# Sheet2.net
KiCad netlist of a schematic drawn in Altium Designer
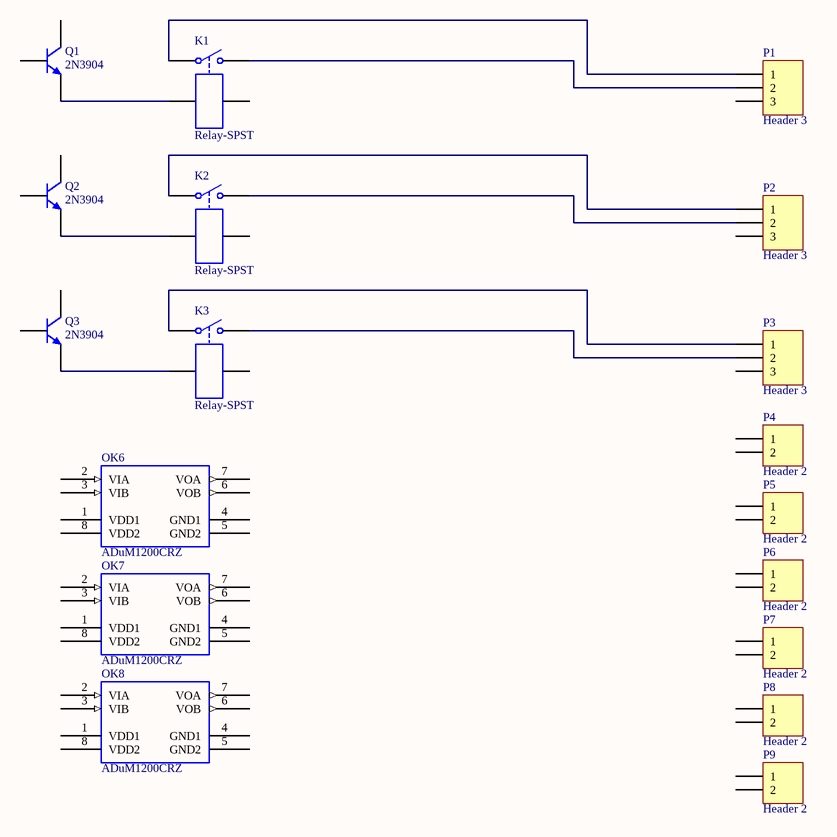
[diagram p0: Sheet2.SchDoc]

(export (version "E")
  (design (tool "Eeschema 10.0.6"))
  (components
    (comp (ref "K1")
      (value "Relay-SPST")
      (footprint "DIP-P4")
      (description "Single-Pole Single-Throw Relay")
      (fields (field (name "PUBLISHER") "Altium Limited"))
      (libsource (lib "Miscellaneous Devices") (part "Relay-SPST"))
    )
    (comp (ref "K2")
      (value "Relay-SPST")
      (footprint "DIP-P4")
      (description "Single-Pole Single-Throw Relay")
      (fields (field (name "PUBLISHER") "Altium Limited"))
      (libsource (lib "Miscellaneous Devices") (part "Relay-SPST"))
    )
    (comp (ref "K3")
      (value "Relay-SPST")
      (footprint "DIP-P4")
      (description "Single-Pole Single-Throw Relay")
      (fields (field (name "PUBLISHER") "Altium Limited"))
      (libsource (lib "Miscellaneous Devices") (part "Relay-SPST"))
    )
    (comp (ref "OK6") (value "ADuM1200CRZ") (libsource (lib "PCB_OBOB") (part "ADuM1200CRZ")))
    (comp (ref "OK7") (value "ADuM1200CRZ") (libsource (lib "PCB_OBOB") (part "ADuM1200CRZ")))
    (comp (ref "OK8") (value "ADuM1200CRZ") (libsource (lib "PCB_OBOB") (part "ADuM1200CRZ")))
    (comp (ref "P1")
      (value "Header 3")
      (footprint "HDR1X3")
      (description "Header, 3-Pin")
      (fields (field (name "PUBLISHER") "Altium Limited"))
      (libsource (lib "Miscellaneous Connectors") (part "Header 3"))
    )
    (comp (ref "P2")
      (value "Header 3")
      (footprint "HDR1X3")
      (description "Header, 3-Pin")
      (fields (field (name "PUBLISHER") "Altium Limited"))
      (libsource (lib "Miscellaneous Connectors") (part "Header 3"))
    )
    (comp (ref "P3")
      (value "Header 3")
      (footprint "HDR1X3")
      (description "Header, 3-Pin")
      (fields (field (name "PUBLISHER") "Altium Limited"))
      (libsource (lib "Miscellaneous Connectors") (part "Header 3"))
    )
    (comp (ref "P4")
      (value "Header 2")
      (footprint "HDR1X2")
      (description "Header, 2-Pin")
      (fields (field (name "PUBLISHER") "Altium Limited"))
      (libsource (lib "Miscellaneous Connectors") (part "Header 2"))
    )
    (comp (ref "P5")
      (value "Header 2")
      (footprint "HDR1X2")
      (description "Header, 2-Pin")
      (fields (field (name "PUBLISHER") "Altium Limited"))
      (libsource (lib "Miscellaneous Connectors") (part "Header 2"))
    )
    (comp (ref "P6")
      (value "Header 2")
      (footprint "HDR1X2")
      (description "Header, 2-Pin")
      (fields (field (name "PUBLISHER") "Altium Limited"))
      (libsource (lib "Miscellaneous Connectors") (part "Header 2"))
    )
    (comp (ref "P7")
      (value "Header 2")
      (footprint "HDR1X2")
      (description "Header, 2-Pin")
      (fields (field (name "PUBLISHER") "Altium Limited"))
      (libsource (lib "Miscellaneous Connectors") (part "Header 2"))
    )
    (comp (ref "P8")
      (value "Header 2")
      (footprint "HDR1X2")
      (description "Header, 2-Pin")
      (fields (field (name "PUBLISHER") "Altium Limited"))
      (libsource (lib "Miscellaneous Connectors") (part "Header 2"))
    )
    (comp (ref "P9")
      (value "Header 2")
      (footprint "HDR1X2")
      (description "Header, 2-Pin")
      (fields (field (name "PUBLISHER") "Altium Limited"))
      (libsource (lib "Miscellaneous Connectors") (part "Header 2"))
    )
    (comp (ref "Q1")
      (value "2N3904")
      (footprint "BCY-W3/E4")
      (description "NPN General Purpose Amplifier")
      (fields (field (name "PUBLISHER") "Altium Limited"))
      (libsource (lib "Miscellaneous Devices") (part "2N3904"))
    )
    (comp (ref "Q2")
      (value "2N3904")
      (footprint "BCY-W3/E4")
      (description "NPN General Purpose Amplifier")
      (fields (field (name "PUBLISHER") "Altium Limited"))
      (libsource (lib "Miscellaneous Devices") (part "2N3904"))
    )
    (comp (ref "Q3")
      (value "2N3904")
      (footprint "BCY-W3/E4")
      (description "NPN General Purpose Amplifier")
      (fields (field (name "PUBLISHER") "Altium Limited"))
      (libsource (lib "Miscellaneous Devices") (part "2N3904"))
    )
  )
  (nets
    (net (code "1") (name "Net-(K1-Pad1)") (class "Default")
      (node (ref "K1") (pin "1") (pinfunction "1_1") (pintype "passive"))
      (node (ref "P1") (pin "1") (pinfunction "1_1") (pintype "passive"))
    )
    (net (code "2") (name "Net-(K1-Pad2)") (class "Default")
      (node (ref "K1") (pin "2") (pinfunction "2_2") (pintype "passive"))
      (node (ref "P1") (pin "2") (pinfunction "2_2") (pintype "passive"))
    )
    (net (code "3") (name "Net-(K2-Pad1)") (class "Default")
      (node (ref "K2") (pin "1") (pinfunction "1_1") (pintype "passive"))
      (node (ref "P2") (pin "1") (pinfunction "1_1") (pintype "passive"))
    )
    (net (code "4") (name "Net-(K2-Pad2)") (class "Default")
      (node (ref "K2") (pin "2") (pinfunction "2_2") (pintype "passive"))
      (node (ref "P2") (pin "2") (pinfunction "2_2") (pintype "passive"))
    )
    (net (code "5") (name "Net-(K3-Pad1)") (class "Default")
      (node (ref "K3") (pin "1") (pinfunction "1_1") (pintype "passive"))
      (node (ref "P3") (pin "1") (pinfunction "1_1") (pintype "passive"))
    )
    (net (code "6") (name "Net-(K3-Pad2)") (class "Default")
      (node (ref "K3") (pin "2") (pinfunction "2_2") (pintype "passive"))
      (node (ref "P3") (pin "2") (pinfunction "2_2") (pintype "passive"))
    )
    (net (code "7") (name "Net-(Q1-E)") (class "Default")
      (node (ref "K1") (pin "3") (pinfunction "3_3") (pintype "passive"))
      (node (ref "Q1") (pin "1") (pinfunction "E_1") (pintype "passive"))
    )
    (net (code "8") (name "Net-(Q2-E)") (class "Default")
      (node (ref "K2") (pin "3") (pinfunction "3_3") (pintype "passive"))
      (node (ref "Q2") (pin "1") (pinfunction "E_1") (pintype "passive"))
    )
    (net (code "9") (name "Net-(Q3-E)") (class "Default")
      (node (ref "K3") (pin "3") (pinfunction "3_3") (pintype "passive"))
      (node (ref "Q3") (pin "1") (pinfunction "E_1") (pintype "passive"))
    )
    (net (code "10") (name "unconnected-(K1-Pad4)") (class "Default")
      (node (ref "K1") (pin "4") (pinfunction "4_4") (pintype "passive"))
    )
    (net (code "11") (name "unconnected-(K2-Pad4)") (class "Default")
      (node (ref "K2") (pin "4") (pinfunction "4_4") (pintype "passive"))
    )
    (net (code "12") (name "unconnected-(K3-Pad4)") (class "Default")
      (node (ref "K3") (pin "4") (pinfunction "4_4") (pintype "passive"))
    )
    (net (code "13") (name "unconnected-(OK6-GND1-Pad4)") (class "Default")
      (node (ref "OK6") (pin "4") (pinfunction "GND1_4") (pintype "power_in"))
    )
    (net (code "14") (name "unconnected-(OK6-GND2-Pad5)") (class "Default")
      (node (ref "OK6") (pin "5") (pinfunction "GND2_5") (pintype "power_in"))
    )
    (net (code "15") (name "unconnected-(OK6-VDD1-Pad1)") (class "Default")
      (node (ref "OK6") (pin "1") (pinfunction "VDD1_1") (pintype "power_in"))
    )
    (net (code "16") (name "unconnected-(OK6-VDD2-Pad8)") (class "Default")
      (node (ref "OK6") (pin "8") (pinfunction "VDD2_8") (pintype "power_in"))
    )
    (net (code "17") (name "unconnected-(OK6-VIA-Pad2)") (class "Default")
      (node (ref "OK6") (pin "2") (pinfunction "VIA_2") (pintype "input"))
    )
    (net (code "18") (name "unconnected-(OK6-VIB-Pad3)") (class "Default")
      (node (ref "OK6") (pin "3") (pinfunction "VIB_3") (pintype "input"))
    )
    (net (code "19") (name "unconnected-(OK6-VOA-Pad7)") (class "Default")
      (node (ref "OK6") (pin "7") (pinfunction "VOA_7") (pintype "output"))
    )
    (net (code "20") (name "unconnected-(OK6-VOB-Pad6)") (class "Default")
      (node (ref "OK6") (pin "6") (pinfunction "VOB_6") (pintype "output"))
    )
    (net (code "21") (name "unconnected-(OK7-GND1-Pad4)") (class "Default")
      (node (ref "OK7") (pin "4") (pinfunction "GND1_4") (pintype "power_in"))
    )
    (net (code "22") (name "unconnected-(OK7-GND2-Pad5)") (class "Default")
      (node (ref "OK7") (pin "5") (pinfunction "GND2_5") (pintype "power_in"))
    )
    (net (code "23") (name "unconnected-(OK7-VDD1-Pad1)") (class "Default")
      (node (ref "OK7") (pin "1") (pinfunction "VDD1_1") (pintype "power_in"))
    )
    (net (code "24") (name "unconnected-(OK7-VDD2-Pad8)") (class "Default")
      (node (ref "OK7") (pin "8") (pinfunction "VDD2_8") (pintype "power_in"))
    )
    (net (code "25") (name "unconnected-(OK7-VIA-Pad2)") (class "Default")
      (node (ref "OK7") (pin "2") (pinfunction "VIA_2") (pintype "input"))
    )
    (net (code "26") (name "unconnected-(OK7-VIB-Pad3)") (class "Default")
      (node (ref "OK7") (pin "3") (pinfunction "VIB_3") (pintype "input"))
    )
    (net (code "27") (name "unconnected-(OK7-VOA-Pad7)") (class "Default")
      (node (ref "OK7") (pin "7") (pinfunction "VOA_7") (pintype "output"))
    )
    (net (code "28") (name "unconnected-(OK7-VOB-Pad6)") (class "Default")
      (node (ref "OK7") (pin "6") (pinfunction "VOB_6") (pintype "output"))
    )
    (net (code "29") (name "unconnected-(OK8-GND1-Pad4)") (class "Default")
      (node (ref "OK8") (pin "4") (pinfunction "GND1_4") (pintype "power_in"))
    )
    (net (code "30") (name "unconnected-(OK8-GND2-Pad5)") (class "Default")
      (node (ref "OK8") (pin "5") (pinfunction "GND2_5") (pintype "power_in"))
    )
    (net (code "31") (name "unconnected-(OK8-VDD1-Pad1)") (class "Default")
      (node (ref "OK8") (pin "1") (pinfunction "VDD1_1") (pintype "power_in"))
    )
    (net (code "32") (name "unconnected-(OK8-VDD2-Pad8)") (class "Default")
      (node (ref "OK8") (pin "8") (pinfunction "VDD2_8") (pintype "power_in"))
    )
    (net (code "33") (name "unconnected-(OK8-VIA-Pad2)") (class "Default")
      (node (ref "OK8") (pin "2") (pinfunction "VIA_2") (pintype "input"))
    )
    (net (code "34") (name "unconnected-(OK8-VIB-Pad3)") (class "Default")
      (node (ref "OK8") (pin "3") (pinfunction "VIB_3") (pintype "input"))
    )
    (net (code "35") (name "unconnected-(OK8-VOA-Pad7)") (class "Default")
      (node (ref "OK8") (pin "7") (pinfunction "VOA_7") (pintype "output"))
    )
    (net (code "36") (name "unconnected-(OK8-VOB-Pad6)") (class "Default")
      (node (ref "OK8") (pin "6") (pinfunction "VOB_6") (pintype "output"))
    )
    (net (code "37") (name "unconnected-(P1-Pad3)") (class "Default")
      (node (ref "P1") (pin "3") (pinfunction "3_3") (pintype "passive"))
    )
    (net (code "38") (name "unconnected-(P2-Pad3)") (class "Default")
      (node (ref "P2") (pin "3") (pinfunction "3_3") (pintype "passive"))
    )
    (net (code "39") (name "unconnected-(P3-Pad3)") (class "Default")
      (node (ref "P3") (pin "3") (pinfunction "3_3") (pintype "passive"))
    )
    (net (code "40") (name "unconnected-(P4-Pad1)") (class "Default")
      (node (ref "P4") (pin "1") (pinfunction "1_1") (pintype "passive"))
    )
    (net (code "41") (name "unconnected-(P4-Pad2)") (class "Default")
      (node (ref "P4") (pin "2") (pinfunction "2_2") (pintype "passive"))
    )
    (net (code "42") (name "unconnected-(P5-Pad1)") (class "Default")
      (node (ref "P5") (pin "1") (pinfunction "1_1") (pintype "passive"))
    )
    (net (code "43") (name "unconnected-(P5-Pad2)") (class "Default")
      (node (ref "P5") (pin "2") (pinfunction "2_2") (pintype "passive"))
    )
    (net (code "44") (name "unconnected-(P6-Pad1)") (class "Default")
      (node (ref "P6") (pin "1") (pinfunction "1_1") (pintype "passive"))
    )
    (net (code "45") (name "unconnected-(P6-Pad2)") (class "Default")
      (node (ref "P6") (pin "2") (pinfunction "2_2") (pintype "passive"))
    )
    (net (code "46") (name "unconnected-(P7-Pad1)") (class "Default")
      (node (ref "P7") (pin "1") (pinfunction "1_1") (pintype "passive"))
    )
    (net (code "47") (name "unconnected-(P7-Pad2)") (class "Default")
      (node (ref "P7") (pin "2") (pinfunction "2_2") (pintype "passive"))
    )
    (net (code "48") (name "unconnected-(P8-Pad1)") (class "Default")
      (node (ref "P8") (pin "1") (pinfunction "1_1") (pintype "passive"))
    )
    (net (code "49") (name "unconnected-(P8-Pad2)") (class "Default")
      (node (ref "P8") (pin "2") (pinfunction "2_2") (pintype "passive"))
    )
    (net (code "50") (name "unconnected-(P9-Pad1)") (class "Default")
      (node (ref "P9") (pin "1") (pinfunction "1_1") (pintype "passive"))
    )
    (net (code "51") (name "unconnected-(P9-Pad2)") (class "Default")
      (node (ref "P9") (pin "2") (pinfunction "2_2") (pintype "passive"))
    )
    (net (code "52") (name "unconnected-(Q1-B-Pad2)") (class "Default")
      (node (ref "Q1") (pin "2") (pinfunction "B_2") (pintype "passive"))
    )
    (net (code "53") (name "unconnected-(Q1-C-Pad3)") (class "Default")
      (node (ref "Q1") (pin "3") (pinfunction "C_3") (pintype "passive"))
    )
    (net (code "54") (name "unconnected-(Q2-B-Pad2)") (class "Default")
      (node (ref "Q2") (pin "2") (pinfunction "B_2") (pintype "passive"))
    )
    (net (code "55") (name "unconnected-(Q2-C-Pad3)") (class "Default")
      (node (ref "Q2") (pin "3") (pinfunction "C_3") (pintype "passive"))
    )
    (net (code "56") (name "unconnected-(Q3-B-Pad2)") (class "Default")
      (node (ref "Q3") (pin "2") (pinfunction "B_2") (pintype "passive"))
    )
    (net (code "57") (name "unconnected-(Q3-C-Pad3)") (class "Default")
      (node (ref "Q3") (pin "3") (pinfunction "C_3") (pintype "passive"))
    )
  )
)
